# ESP_Sheild.net
KiCad netlist of a schematic drawn in Altium Designer
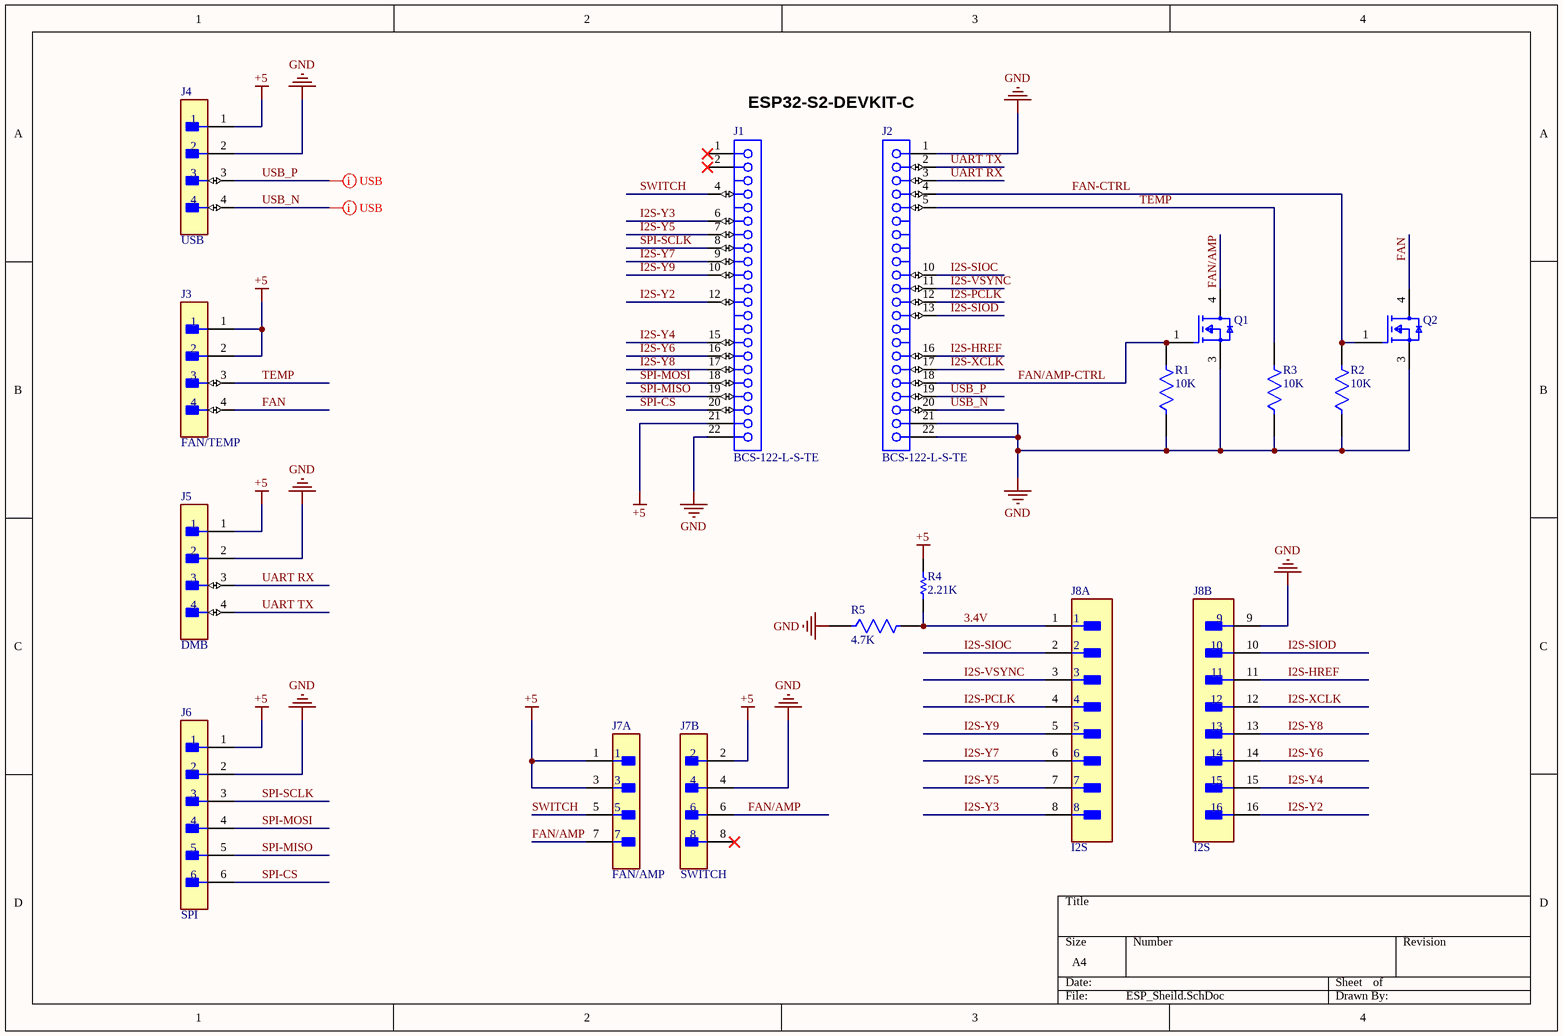
[diagram p0: ESP_Sheild.SchDoc]

(export (version "E")
  (design (tool "Eeschema 10.0.6"))
  (components
    (comp (ref "J1")
      (value "BCS-122-L-S-TE")
      (footprint "SMTC-BCS-122-X-S-TE")
      (description "Conn Socket Strip SKT 22 POS 2.54mm Solder ST Thru-Hole Tube")
      (libsource (lib "Mac's Projects") (part "SMTC-BCS-122-X-S-TE"))
    )
    (comp (ref "J2")
      (value "BCS-122-L-S-TE")
      (footprint "SMTC-BCS-122-X-S-TE")
      (description "Conn Socket Strip SKT 22 POS 2.54mm Solder ST Thru-Hole Tube")
      (libsource (lib "Mac's Projects") (part "SMTC-BCS-122-X-S-TE"))
    )
    (comp (ref "J3")
      (value "FAN/TEMP")
      (footprint "FP-43045-0400-MFG")
      (description "CONN HEADER R/A 4POS 3MM\r\n\r\nFAN/THERMISISTOR")
      (fields (field (name "MANUFACTURER PART NUMBER") "43045-0400") (field (name "MANUFACTURER") "Molex"))
      (libsource (lib "") (part "c01754ab0efc13afb7424b896f394ef_2"))
    )
    (comp (ref "J4")
      (value "USB")
      (footprint "FP-43045-0400-MFG")
      (description "CONN HEADER R/A 4POS 3MM")
      (fields (field (name "MANUFACTURER PART NUMBER") "43045-0400") (field (name "MANUFACTURER") "Molex"))
      (libsource (lib "Altium Content Vault") (part "c01754ab0efc13afb7424b896f394ef"))
    )
    (comp (ref "J5")
      (value "DMB")
      (footprint "FP-43045-0400-MFG")
      (description "CONN HEADER R/A 4POS 3MM\r\n\r\nDMB UART")
      (fields (field (name "MANUFACTURER PART NUMBER") "43045-0400") (field (name "MANUFACTURER") "Molex"))
      (libsource (lib "") (part "c01754ab0efc13afb7424b896f394ef_1"))
    )
    (comp (ref "J6")
      (value "SPI")
      (footprint "FP-43045-0612-MFG")
      (description "CONN HEADER VERT 6POS 3MM")
      (libsource (lib "Altium Content Vault") (part "11692be1245668b174829cb8722fdf5"))
    )
    (comp (ref "J7")
      (value "FAN/AMP")
      (footprint "FP-43045-0827-0")
      (description "CONN HEADER VERT 8POS 3MM")
      (libsource (lib "") (part "254f1a2ef83cf916f492965d8f0ded1_1"))
    )
    (comp (ref "J8")
      (value "I2S")
      (footprint "FP-1723161216-MFG")
      (description "CONN HEADER R/A 16POS 3.5MM")
      (fields
        (field (name "MANUFACTURER PART NUMBER") "1723161216")
        (field (name "OCTOPART") "https://octopart.com/172316-1216-molex-60760060")
      )
      (libsource (lib "Altium Content Vault") (part "91eeaff556776ba2144699b5bd25858"))
    )
    (comp (ref "Q1")
      (value "DMN6068LK3-13")
      (footprint "FP-TO252_DPAK-MFG")
      (description "VDS=60V VGS=±20V ID=8.5A P=2.12W")
      (libsource (lib "Mac's Projects") (part "86656c45bbbddc162aead764a772c09"))
    )
    (comp (ref "Q2")
      (value "DMN6068LK3-13")
      (footprint "FP-TO252_DPAK-MFG")
      (description "VDS=60V VGS=±20V ID=8.5A P=2.12W")
      (libsource (lib "Mac's Projects") (part "86656c45bbbddc162aead764a772c09"))
    )
    (comp (ref "R1")
      (value "10K")
      (footprint "FP-ERJ3G-IPC_A")
      (description "贴片电阻 10KΩ ±5% 1/10W ±200ppm/℃ 0603")
      (fields (field (name "TOLERANCE") "5%"))
      (libsource (lib "Mac's Projects") (part "1029c3af85768c4190bb7ad29bc67b5"))
    )
    (comp (ref "R2")
      (value "10K")
      (footprint "FP-ERJ3G-IPC_A")
      (description "贴片电阻 10KΩ ±5% 1/10W ±200ppm/℃ 0603")
      (fields (field (name "TOLERANCE") "5%"))
      (libsource (lib "Mac's Projects") (part "1029c3af85768c4190bb7ad29bc67b5"))
    )
    (comp (ref "R3")
      (value "10K")
      (footprint "FP-ERJ3G-IPC_A")
      (description "贴片电阻 10KΩ ±5% 1/10W ±200ppm/℃ 0603")
      (fields (field (name "TOLERANCE") "5%"))
      (libsource (lib "Mac's Projects") (part "1029c3af85768c4190bb7ad29bc67b5"))
    )
    (comp (ref "R4")
      (value "2.21K")
      (footprint "RESC1608X55X30LL15T15")
      (description "Res Thick Film 0603 2.21K Ohm 1% 1/10W +/-100ppm/ßC Molded SMD Punched Carrier T/R")
      (fields (field (name "TOLERANCE") "1%"))
      (libsource (lib "Mac's Projects") (part "RES"))
    )
    (comp (ref "R5")
      (value "4.7K")
      (footprint "FP-RMCF0603-MFG")
      (description "Resistor Thick Film 0603 4.7K Ohm 1% 1/10W ±100ppm/°C Molded SMD SMD Paper T/R")
      (fields (field (name "TOLERANCE") "1%"))
      (libsource (lib "Mac's Projects") (part "1029c3af85768c4190bb7ad29bc67b5"))
    )
  )
  (nets
    (net (code "1") (name "+5") (class "Default")
      (node (ref "J1") (pin "21") (pinfunction "5V_21") (pintype "power_in"))
      (node (ref "J3") (pin "1") (pinfunction "5V_1") (pintype "power_in"))
      (node (ref "J3") (pin "2") (pinfunction "5V_2") (pintype "power_in"))
      (node (ref "J4") (pin "1") (pinfunction "5V_1") (pintype "power_in"))
      (node (ref "J5") (pin "1") (pinfunction "5V_1") (pintype "power_in"))
      (node (ref "J6") (pin "1") (pinfunction "5V_1") (pintype "power_in"))
      (node (ref "J7") (pin "1") (pinfunction "5V_1") (pintype "power_in"))
      (node (ref "J7") (pin "2") (pinfunction "2_2") (pintype "passive"))
      (node (ref "J7") (pin "3") (pinfunction "5V_3") (pintype "power_in"))
      (node (ref "R4") (pin "2") (pinfunction "2_2") (pintype "passive"))
    )
    (net (code "2") (name "/3.4V") (class "Default")
      (node (ref "J8") (pin "1") (pinfunction "3V3_1") (pintype "power_in"))
      (node (ref "R4") (pin "1") (pinfunction "1_1") (pintype "passive"))
      (node (ref "R5") (pin "2") (pinfunction "2_2") (pintype "passive"))
    )
    (net (code "3") (name "/FAN") (class "Default")
      (node (ref "J3") (pin "4") (pinfunction "FAN_4") (pintype "bidirectional"))
      (node (ref "Q2") (pin "4") (pinfunction "D_4") (pintype "passive"))
    )
    (net (code "4") (name "/FAN-CTRL") (class "Default")
      (node (ref "J2") (pin "4") (pinfunction "GPIO4_4") (pintype "bidirectional"))
      (node (ref "Q2") (pin "1") (pinfunction "G_1") (pintype "passive"))
      (node (ref "R2") (pin "2") (pinfunction "2_2") (pintype "passive"))
    )
    (net (code "5") (name "/FAN{slash}AMP") (class "Default")
      (node (ref "J7") (pin "6") (pinfunction "6_6") (pintype "passive"))
      (node (ref "J7") (pin "7") (pinfunction "FAN/AMP_7") (pintype "passive"))
      (node (ref "Q1") (pin "4") (pinfunction "D_4") (pintype "passive"))
    )
    (net (code "6") (name "/FAN{slash}AMP-CTRL") (class "Default")
      (node (ref "J2") (pin "18") (pinfunction "GPIO12_18") (pintype "bidirectional"))
      (node (ref "Q1") (pin "1") (pinfunction "G_1") (pintype "passive"))
      (node (ref "R1") (pin "2") (pinfunction "2_2") (pintype "passive"))
    )
    (net (code "7") (name "/I2S-HREF") (class "Default")
      (node (ref "J2") (pin "16") (pinfunction "GPIO10_16") (pintype "bidirectional"))
      (node (ref "J8") (pin "11") (pinfunction "11_11") (pintype "passive"))
    )
    (net (code "8") (name "/I2S-PCLK") (class "Default")
      (node (ref "J2") (pin "12") (pinfunction "GPIO8_12") (pintype "bidirectional"))
      (node (ref "J8") (pin "4") (pinfunction "VSYNC_4") (pintype "passive"))
    )
    (net (code "9") (name "/I2S-SIOC") (class "Default")
      (node (ref "J2") (pin "10") (pinfunction "GPIO17_10") (pintype "bidirectional"))
      (node (ref "J8") (pin "2") (pinfunction "PCLK_2") (pintype "passive"))
    )
    (net (code "10") (name "/I2S-SIOD") (class "Default")
      (node (ref "J2") (pin "13") (pinfunction "GPIO3_13") (pintype "bidirectional"))
      (node (ref "J8") (pin "10") (pinfunction "10_10") (pintype "passive"))
    )
    (net (code "11") (name "/I2S-VSYNC") (class "Default")
      (node (ref "J2") (pin "11") (pinfunction "GPIO18_11") (pintype "bidirectional"))
      (node (ref "J8") (pin "3") (pinfunction "HREF_3") (pintype "passive"))
    )
    (net (code "12") (name "/I2S-XCLK") (class "Default")
      (node (ref "J2") (pin "17") (pinfunction "GPIO11_17") (pintype "bidirectional"))
      (node (ref "J8") (pin "12") (pinfunction "12_12") (pintype "passive"))
    )
    (net (code "13") (name "/I2S-Y2") (class "Default")
      (node (ref "J1") (pin "12") (pinfunction "GPIO8_12") (pintype "bidirectional"))
      (node (ref "J8") (pin "16") (pinfunction "16_16") (pintype "passive"))
    )
    (net (code "14") (name "/I2S-Y3") (class "Default")
      (node (ref "J1") (pin "6") (pinfunction "GPIO6_6") (pintype "bidirectional"))
      (node (ref "J8") (pin "8") (pinfunction "Y2_8") (pintype "passive"))
    )
    (net (code "15") (name "/I2S-Y4") (class "Default")
      (node (ref "J1") (pin "15") (pinfunction "GPIO9_15") (pintype "bidirectional"))
      (node (ref "J8") (pin "15") (pinfunction "15_15") (pintype "passive"))
    )
    (net (code "16") (name "/I2S-Y5") (class "Default")
      (node (ref "J1") (pin "7") (pinfunction "GPIO7_7") (pintype "bidirectional"))
      (node (ref "J8") (pin "7") (pinfunction "XCLK_7") (pintype "passive"))
    )
    (net (code "17") (name "/I2S-Y6") (class "Default")
      (node (ref "J1") (pin "16") (pinfunction "GPIO10_16") (pintype "bidirectional"))
      (node (ref "J8") (pin "14") (pinfunction "14_14") (pintype "passive"))
    )
    (net (code "18") (name "/I2S-Y7") (class "Default")
      (node (ref "J1") (pin "9") (pinfunction "GPIO16_9") (pintype "bidirectional"))
      (node (ref "J8") (pin "6") (pinfunction "SIOD_6") (pintype "passive"))
    )
    (net (code "19") (name "/I2S-Y8") (class "Default")
      (node (ref "J1") (pin "17") (pinfunction "GPIO11_17") (pintype "bidirectional"))
      (node (ref "J8") (pin "13") (pinfunction "13_13") (pintype "passive"))
    )
    (net (code "20") (name "/I2S-Y9") (class "Default")
      (node (ref "J1") (pin "10") (pinfunction "GPIO17_10") (pintype "bidirectional"))
      (node (ref "J8") (pin "5") (pinfunction "SIOC_5") (pintype "passive"))
    )
    (net (code "21") (name "/SPI-CS") (class "Default")
      (node (ref "J1") (pin "20") (pinfunction "GPIO14_20") (pintype "bidirectional"))
      (node (ref "J6") (pin "6") (pinfunction "CS_6") (pintype "passive"))
    )
    (net (code "22") (name "/SPI-MISO") (class "Default")
      (node (ref "J1") (pin "19") (pinfunction "GPIO13_19") (pintype "bidirectional"))
      (node (ref "J6") (pin "5") (pinfunction "MISO_5") (pintype "passive"))
    )
    (net (code "23") (name "/SPI-MOSI") (class "Default")
      (node (ref "J1") (pin "18") (pinfunction "GPIO12_18") (pintype "bidirectional"))
      (node (ref "J6") (pin "4") (pinfunction "MOSI_4") (pintype "passive"))
    )
    (net (code "24") (name "/SPI-SCLK") (class "Default")
      (node (ref "J1") (pin "8") (pinfunction "GPIO15_8") (pintype "bidirectional"))
      (node (ref "J6") (pin "3") (pinfunction "SCLK_3") (pintype "passive"))
    )
    (net (code "25") (name "/SWITCH") (class "Default")
      (node (ref "J1") (pin "4") (pinfunction "GPIO4_4") (pintype "bidirectional"))
      (node (ref "J7") (pin "5") (pinfunction "FAN/AMP_5") (pintype "passive"))
    )
    (net (code "26") (name "/TEMP") (class "Default")
      (node (ref "J2") (pin "5") (pinfunction "GPIO5_5") (pintype "bidirectional"))
      (node (ref "J3") (pin "3") (pinfunction "TEMP_3") (pintype "bidirectional"))
      (node (ref "R3") (pin "2") (pinfunction "2_2") (pintype "passive"))
    )
    (net (code "27") (name "/UART RX") (class "Default")
      (node (ref "J2") (pin "3") (pinfunction "RST_3") (pintype "passive"))
      (node (ref "J5") (pin "3") (pinfunction "UART-TX_3") (pintype "bidirectional"))
    )
    (net (code "28") (name "/UART TX") (class "Default")
      (node (ref "J2") (pin "2") (pinfunction "3V3_2") (pintype "power_in"))
      (node (ref "J5") (pin "4") (pinfunction "UART-RX_4") (pintype "bidirectional"))
    )
    (net (code "29") (name "/USB_N") (class "Default")
      (node (ref "J2") (pin "20") (pinfunction "GPIO14_20") (pintype "bidirectional"))
      (node (ref "J4") (pin "4") (pinfunction "4_4") (pintype "bidirectional"))
    )
    (net (code "30") (name "/USB_P") (class "Default")
      (node (ref "J2") (pin "19") (pinfunction "GPIO13_19") (pintype "bidirectional"))
      (node (ref "J4") (pin "3") (pinfunction "3_3") (pintype "bidirectional"))
    )
    (net (code "31") (name "GND") (class "Default")
      (node (ref "J1") (pin "22") (pinfunction "GND_22") (pintype "power_in"))
      (node (ref "J2") (pin "1") (pinfunction "3V3_1") (pintype "power_in"))
      (node (ref "J2") (pin "21") (pinfunction "5V_21") (pintype "power_in"))
      (node (ref "J2") (pin "22") (pinfunction "GND_22") (pintype "power_in"))
      (node (ref "J4") (pin "2") (pinfunction "GND_2") (pintype "power_in"))
      (node (ref "J5") (pin "2") (pinfunction "GND_2") (pintype "power_in"))
      (node (ref "J6") (pin "2") (pinfunction "GND_2") (pintype "power_in"))
      (node (ref "J7") (pin "4") (pinfunction "4_4") (pintype "passive"))
      (node (ref "J8") (pin "9") (pinfunction "9_9") (pintype "passive"))
      (node (ref "Q1") (pin "3") (pinfunction "S_3") (pintype "passive"))
      (node (ref "Q2") (pin "3") (pinfunction "S_3") (pintype "passive"))
      (node (ref "R1") (pin "1") (pinfunction "1_1") (pintype "passive"))
      (node (ref "R2") (pin "1") (pinfunction "1_1") (pintype "passive"))
      (node (ref "R3") (pin "1") (pinfunction "1_1") (pintype "passive"))
      (node (ref "R5") (pin "1") (pinfunction "1_1") (pintype "passive"))
    )
    (net (code "32") (name "unconnected-(J1-3V3-Pad1)") (class "Default")
      (node (ref "J1") (pin "1") (pinfunction "3V3_1") (pintype "power_in+no_connect"))
    )
    (net (code "33") (name "unconnected-(J1-3V3-Pad2)") (class "Default")
      (node (ref "J1") (pin "2") (pinfunction "3V3_2") (pintype "power_in+no_connect"))
    )
    (net (code "34") (name "unconnected-(J1-GPIO3-Pad13)") (class "Default")
      (node (ref "J1") (pin "13") (pinfunction "GPIO3_13") (pintype "bidirectional"))
    )
    (net (code "35") (name "unconnected-(J1-GPIO5-Pad5)") (class "Default")
      (node (ref "J1") (pin "5") (pinfunction "GPIO5_5") (pintype "bidirectional"))
    )
    (net (code "36") (name "unconnected-(J1-GPIO18-Pad11)") (class "Default")
      (node (ref "J1") (pin "11") (pinfunction "GPIO18_11") (pintype "bidirectional"))
    )
    (net (code "37") (name "unconnected-(J1-GPIO46-Pad14)") (class "Default")
      (node (ref "J1") (pin "14") (pinfunction "GPIO46_14") (pintype "bidirectional"))
    )
    (net (code "38") (name "unconnected-(J1-RST-Pad3)") (class "Default")
      (node (ref "J1") (pin "3") (pinfunction "RST_3") (pintype "passive"))
    )
    (net (code "39") (name "unconnected-(J2-GPIO6-Pad6)") (class "Default")
      (node (ref "J2") (pin "6") (pinfunction "GPIO6_6") (pintype "bidirectional"))
    )
    (net (code "40") (name "unconnected-(J2-GPIO7-Pad7)") (class "Default")
      (node (ref "J2") (pin "7") (pinfunction "GPIO7_7") (pintype "bidirectional"))
    )
    (net (code "41") (name "unconnected-(J2-GPIO9-Pad15)") (class "Default")
      (node (ref "J2") (pin "15") (pinfunction "GPIO9_15") (pintype "bidirectional"))
    )
    (net (code "42") (name "unconnected-(J2-GPIO15-Pad8)") (class "Default")
      (node (ref "J2") (pin "8") (pinfunction "GPIO15_8") (pintype "bidirectional"))
    )
    (net (code "43") (name "unconnected-(J2-GPIO16-Pad9)") (class "Default")
      (node (ref "J2") (pin "9") (pinfunction "GPIO16_9") (pintype "bidirectional"))
    )
    (net (code "44") (name "unconnected-(J2-GPIO46-Pad14)") (class "Default")
      (node (ref "J2") (pin "14") (pinfunction "GPIO46_14") (pintype "bidirectional"))
    )
    (net (code "45") (name "unconnected-(J7-Pad8)") (class "Default")
      (node (ref "J7") (pin "8") (pinfunction "8_8") (pintype "passive+no_connect"))
    )
  )
)
